# Stick_IMUinator_v2_1.net
KiCad netlist of a schematic drawn in EAGLE
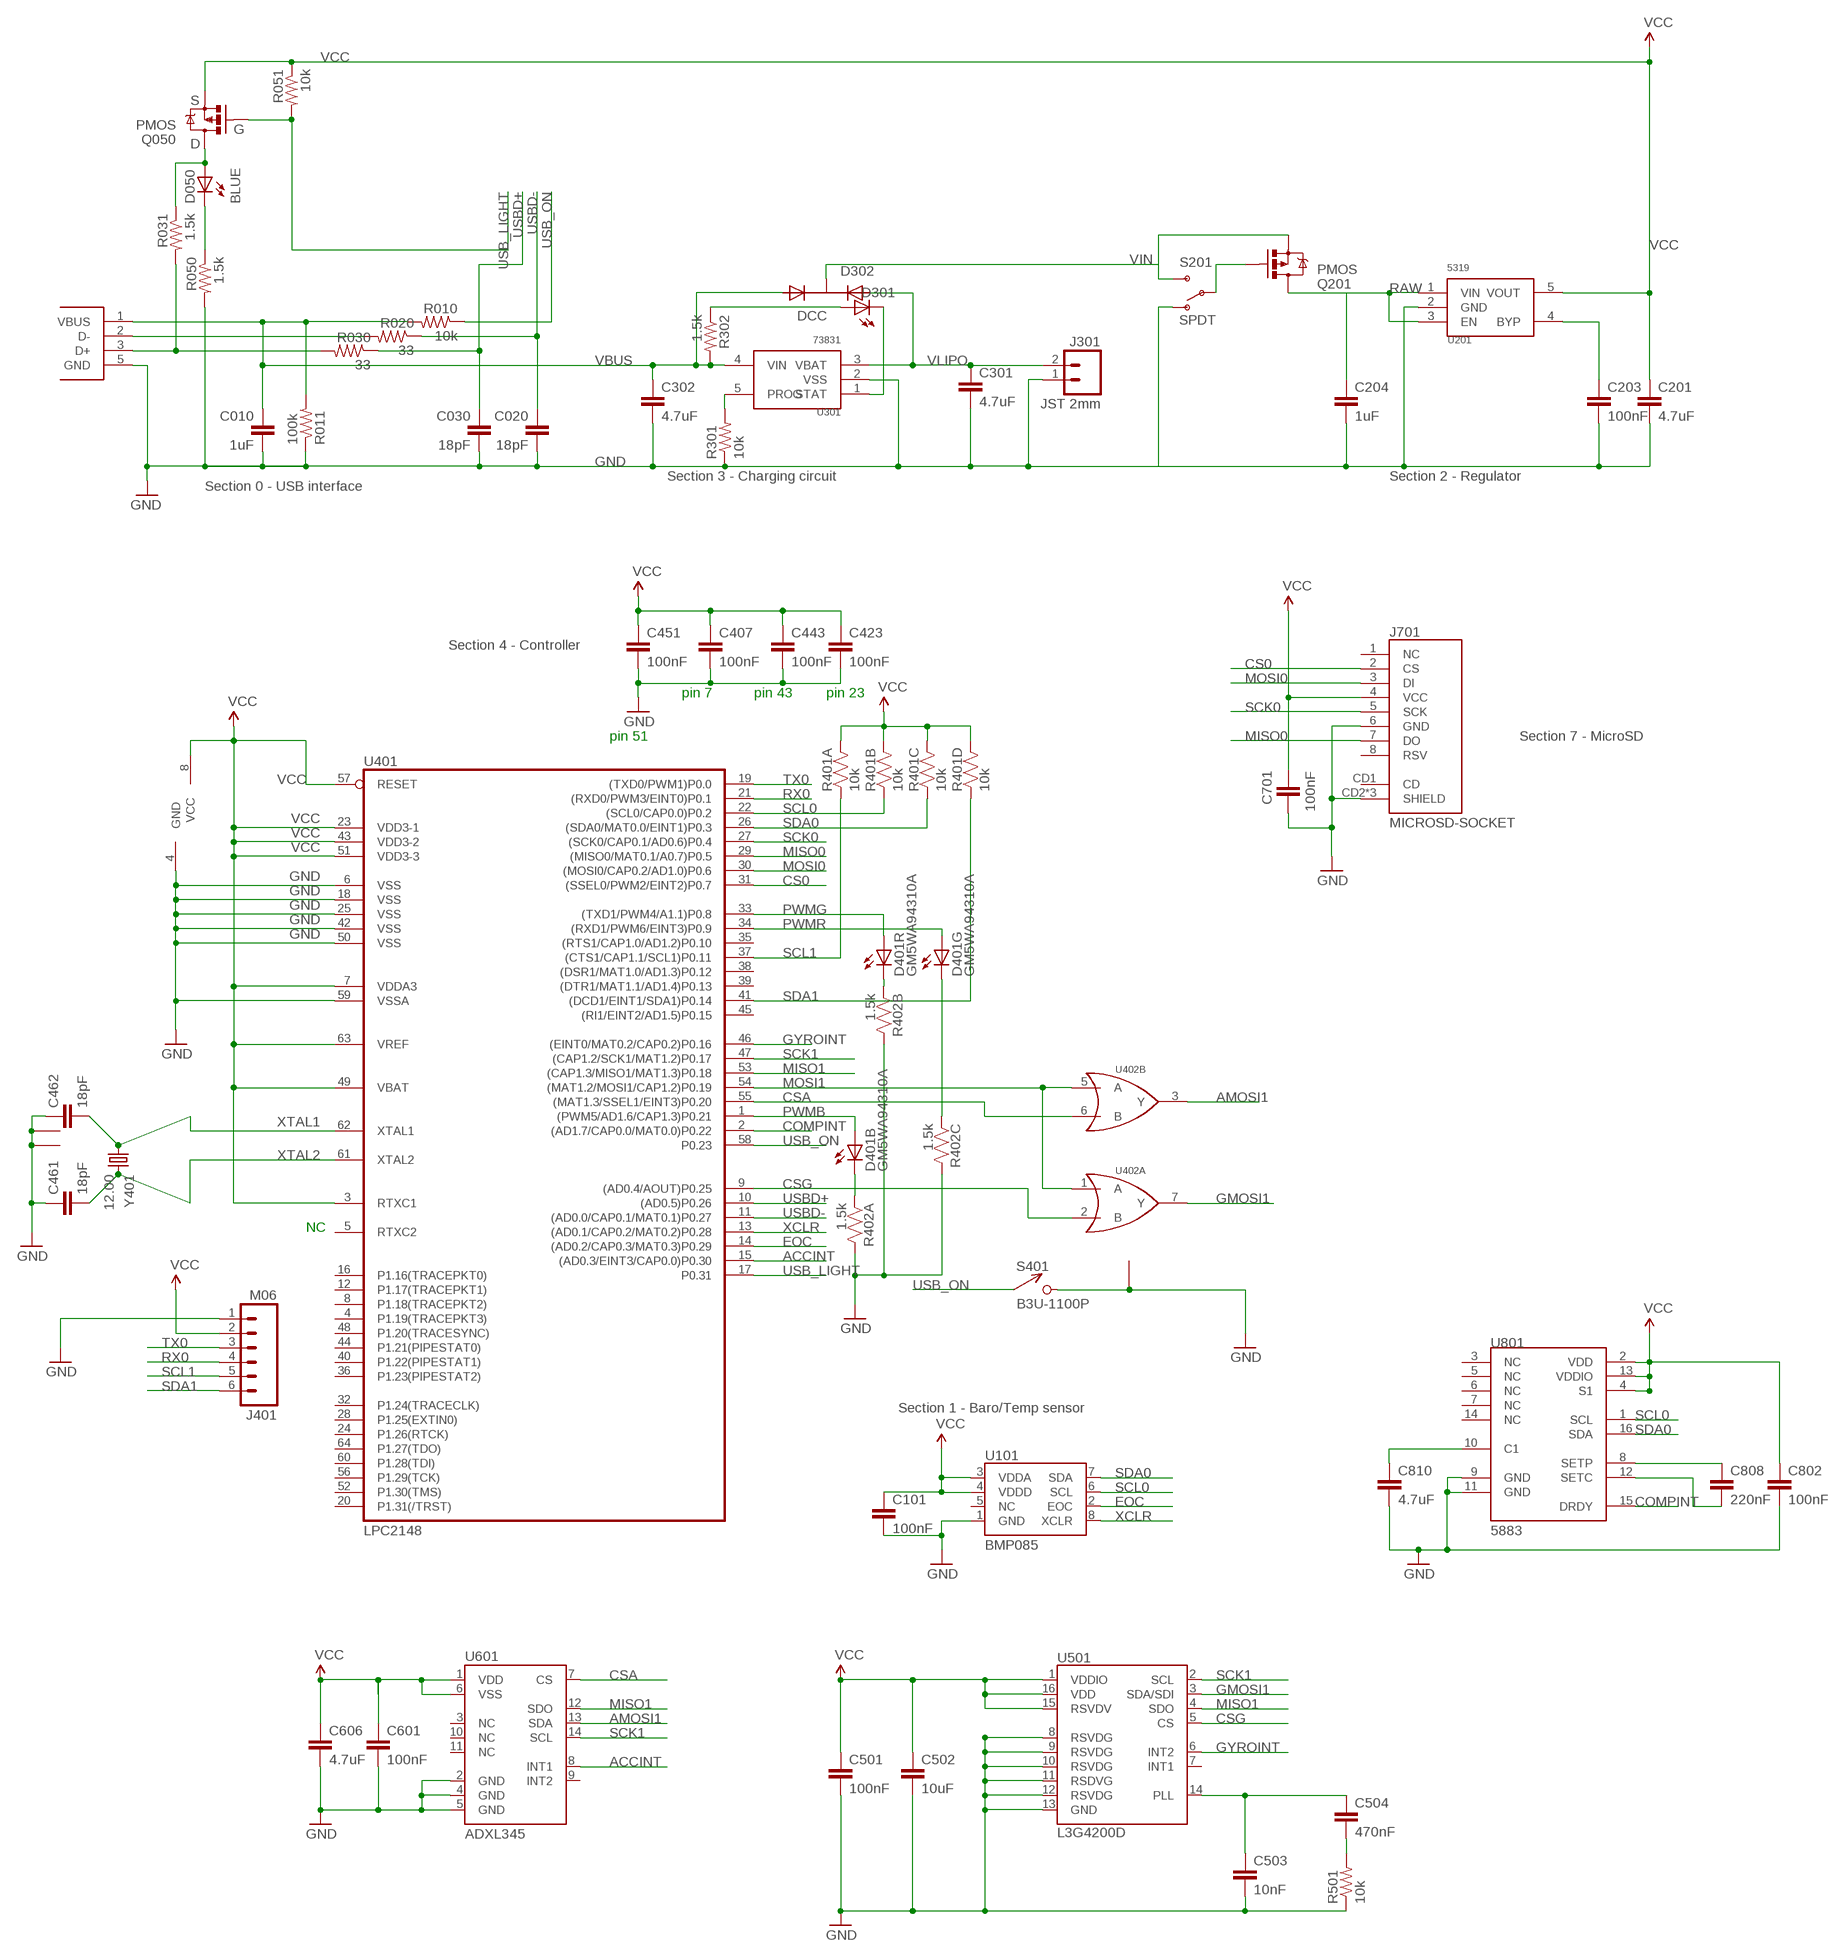
[diagram p0: schematic, sheet 1]

(export (version "E")
  (design (tool "Eeschema 10.0.6"))
  (components
    (comp (ref "C010")
      (value "1uF")
      (footprint "eagle-import:0402-CAP")
      (libsource (lib "eagle-import") (part "CAP0402-CAP"))
    )
    (comp (ref "C020")
      (value "18pF")
      (footprint "eagle-import:0402-CAP")
      (libsource (lib "eagle-import") (part "CAP0402-CAP"))
    )
    (comp (ref "C030")
      (value "18pF")
      (footprint "eagle-import:0402-CAP")
      (libsource (lib "eagle-import") (part "CAP0402-CAP"))
    )
    (comp (ref "C101")
      (value "100nF")
      (footprint "eagle-import:0402-CAP")
      (libsource (lib "eagle-import") (part "CAP0402-CAP"))
    )
    (comp (ref "C201")
      (value "4.7uF")
      (footprint "eagle-import:0402-CAP")
      (libsource (lib "eagle-import") (part "CAP0402-CAP"))
    )
    (comp (ref "C203")
      (value "100nF")
      (footprint "eagle-import:0402-CAP")
      (libsource (lib "eagle-import") (part "CAP0402-CAP"))
    )
    (comp (ref "C204")
      (value "1uF")
      (footprint "eagle-import:0402-CAP")
      (libsource (lib "eagle-import") (part "CAP0402-CAP"))
    )
    (comp (ref "C301")
      (value "4.7uF")
      (footprint "eagle-import:0402-CAP")
      (libsource (lib "eagle-import") (part "CAP0402-CAP"))
    )
    (comp (ref "C302")
      (value "4.7uF")
      (footprint "eagle-import:0402-CAP")
      (libsource (lib "eagle-import") (part "CAP0402-CAP"))
    )
    (comp (ref "C407")
      (value "100nF")
      (footprint "eagle-import:0402-CAP")
      (libsource (lib "eagle-import") (part "CAP0402-CAP"))
    )
    (comp (ref "C423")
      (value "100nF")
      (footprint "eagle-import:0402-CAP")
      (libsource (lib "eagle-import") (part "CAP0402-CAP"))
    )
    (comp (ref "C443")
      (value "100nF")
      (footprint "eagle-import:0402-CAP")
      (libsource (lib "eagle-import") (part "CAP0402-CAP"))
    )
    (comp (ref "C451")
      (value "100nF")
      (footprint "eagle-import:0402-CAP")
      (libsource (lib "eagle-import") (part "CAP0402-CAP"))
    )
    (comp (ref "C461")
      (value "18pF")
      (footprint "eagle-import:0402-CAP")
      (libsource (lib "eagle-import") (part "CAP0402-CAP"))
    )
    (comp (ref "C462")
      (value "18pF")
      (footprint "eagle-import:0402-CAP")
      (libsource (lib "eagle-import") (part "CAP0402-CAP"))
    )
    (comp (ref "C501")
      (value "100nF")
      (footprint "eagle-import:0402-CAP")
      (libsource (lib "eagle-import") (part "CAP0402-CAP"))
    )
    (comp (ref "C502")
      (value "10uF")
      (footprint "eagle-import:0603-CAP")
      (libsource (lib "eagle-import") (part "CAP0603-CAP"))
    )
    (comp (ref "C503")
      (value "10nF")
      (footprint "eagle-import:0402-CAP")
      (libsource (lib "eagle-import") (part "CAP0402-CAP"))
    )
    (comp (ref "C504")
      (value "470nF")
      (footprint "eagle-import:0402-CAP")
      (libsource (lib "eagle-import") (part "CAP0402-CAP"))
    )
    (comp (ref "C601")
      (value "100nF")
      (footprint "eagle-import:0402-CAP")
      (libsource (lib "eagle-import") (part "CAP0402-CAP"))
    )
    (comp (ref "C606")
      (value "4.7uF")
      (footprint "eagle-import:0402-CAP")
      (libsource (lib "eagle-import") (part "CAP0402-CAP"))
    )
    (comp (ref "C701")
      (value "100nF")
      (footprint "eagle-import:0402-CAP")
      (libsource (lib "eagle-import") (part "CAP0402-CAP"))
    )
    (comp (ref "C802")
      (value "100nF")
      (footprint "eagle-import:0402-CAP")
      (libsource (lib "eagle-import") (part "CAP0402-CAP"))
    )
    (comp (ref "C808")
      (value "220nF")
      (footprint "eagle-import:0402-CAP")
      (libsource (lib "eagle-import") (part "CAP0402-CAP"))
    )
    (comp (ref "C810")
      (value "4.7uF")
      (footprint "eagle-import:0402-CAP")
      (libsource (lib "eagle-import") (part "CAP0402-CAP"))
    )
    (comp (ref "D050")
      (value "BLUE")
      (footprint "eagle-import:LED-0603")
      (libsource (lib "eagle-import") (part "LED0603"))
    )
    (comp (ref "D301")
      (value "YELLOW")
      (footprint "eagle-import:LED-0603")
      (libsource (lib "eagle-import") (part "LED0603"))
    )
    (comp (ref "D302")
      (value "DCC")
      (footprint "eagle-import:SOT-23-3")
      (libsource (lib "eagle-import") (part "PMEG2005CT"))
    )
    (comp (ref "D401")
      (value "GM5WA94310A")
      (footprint "eagle-import:GM5WA94310A")
      (fields (field (name "DIGIKEY") "425-2728-1-ND"))
      (libsource (lib "eagle-import") (part "GM5WA94310A"))
    )
    (comp (ref "J001")
      (value "USB_MICROB_JST")
      (footprint "eagle-import:UB-MC5BR3-SD204-4S")
      (libsource (lib "eagle-import") (part "USB_MICROB_JST"))
    )
    (comp (ref "J301")
      (value "JST 2mm")
      (footprint "eagle-import:JST-2-SMD")
      (libsource (lib "eagle-import") (part "M02-JST-2MM-SMT"))
    )
    (comp (ref "J401")
      (value "M06")
      (footprint "eagle-import:1X06_LOCK")
      (libsource (lib "eagle-import") (part "M06LOCK"))
    )
    (comp (ref "J701")
      (value "MICROSD-SOCKET")
      (footprint "eagle-import:MICROSD-SOCKET-PP")
      (libsource (lib "eagle-import") (part "MICROSD-SOCKET"))
    )
    (comp (ref "Q050")
      (value "PMOS")
      (footprint "eagle-import:SOT23-3")
      (libsource (lib "eagle-import") (part "MOSFET-PCHANNELSMD"))
    )
    (comp (ref "Q201")
      (value "PMOS")
      (footprint "eagle-import:SOT23-3")
      (libsource (lib "eagle-import") (part "MOSFET-PCHANNELSMD"))
    )
    (comp (ref "R010")
      (value "10k")
      (footprint "eagle-import:0402-RES")
      (libsource (lib "eagle-import") (part "RESISTOR0402-RES"))
    )
    (comp (ref "R011")
      (value "100k")
      (footprint "eagle-import:0402-RES")
      (libsource (lib "eagle-import") (part "RESISTOR0402-RES"))
    )
    (comp (ref "R020")
      (value "33")
      (footprint "eagle-import:0402-RES")
      (libsource (lib "eagle-import") (part "RESISTOR0402-RES"))
    )
    (comp (ref "R030")
      (value "33")
      (footprint "eagle-import:0402-RES")
      (libsource (lib "eagle-import") (part "RESISTOR0402-RES"))
    )
    (comp (ref "R031")
      (value "1.5k")
      (footprint "eagle-import:0402-RES")
      (libsource (lib "eagle-import") (part "RESISTOR0402-RES"))
    )
    (comp (ref "R050")
      (value "1.5k")
      (footprint "eagle-import:0402-RES")
      (libsource (lib "eagle-import") (part "RESISTOR0402-RES"))
    )
    (comp (ref "R051")
      (value "10k")
      (footprint "eagle-import:0402-RES")
      (libsource (lib "eagle-import") (part "RESISTOR0402-RES"))
    )
    (comp (ref "R301")
      (value "10k")
      (footprint "eagle-import:0402-RES")
      (libsource (lib "eagle-import") (part "RESISTOR0402-RES"))
    )
    (comp (ref "R302")
      (value "1.5k")
      (footprint "eagle-import:0402-RES")
      (libsource (lib "eagle-import") (part "RESISTOR0402-RES"))
    )
    (comp (ref "R401")
      (value "10k")
      (footprint "eagle-import:CRA04")
      (fields (field (name "DIGIKEY") "CRA4S810KCT-ND"))
      (libsource (lib "eagle-import") (part "RP404"))
    )
    (comp (ref "R402")
      (value "1.5k")
      (footprint "eagle-import:CRA04")
      (fields (field (name "DIGIKEY") "CRA4S81.5KCT-ND"))
      (libsource (lib "eagle-import") (part "RP404"))
    )
    (comp (ref "R501")
      (value "10k")
      (footprint "eagle-import:0402-RES")
      (libsource (lib "eagle-import") (part "RESISTOR0402-RES"))
    )
    (comp (ref "S201")
      (value "SPDT")
      (footprint "eagle-import:AYZ0202")
      (libsource (lib "eagle-import") (part "SWITCH-SPSTSMD"))
    )
    (comp (ref "S401")
      (value "B3U-1100P")
      (footprint "eagle-import:B3U-1100P")
      (fields (field (name "DIGIKEY") "SW1021CT-ND"))
      (libsource (lib "eagle-import") (part "B3U-1100P"))
    )
    (comp (ref "U101")
      (value "BMP085")
      (footprint "eagle-import:BMP085")
      (libsource (lib "eagle-import") (part "BMP085"))
    )
    (comp (ref "U201")
      (value "5319")
      (footprint "eagle-import:SOT-23-5")
      (libsource (lib "eagle-import") (part "MIC5319D5"))
    )
    (comp (ref "U301")
      (value "73831")
      (footprint "eagle-import:SOT-23-5")
      (libsource (lib "eagle-import") (part "MCP73831"))
    )
    (comp (ref "U401")
      (value "LPC2148")
      (footprint "eagle-import:SQFP-S-10X10-64")
      (libsource (lib "eagle-import") (part "LPC213X"))
    )
    (comp (ref "U402")
      (value "7432")
      (footprint "eagle-import:DCU_8")
      (fields (field (name "DIGIKEY") "296-13268-1-ND"))
      (libsource (lib "eagle-import") (part "SN74LVC2G32"))
    )
    (comp (ref "U501")
      (value "L3G4200D")
      (footprint "eagle-import:LGA16-4X4")
      (libsource (lib "eagle-import") (part "L3G4200D"))
    )
    (comp (ref "U601")
      (value "ADXL345")
      (footprint "eagle-import:LGA14")
      (libsource (lib "eagle-import") (part "ADXL345"))
    )
    (comp (ref "U801")
      (value "5883")
      (footprint "eagle-import:16LPCC")
      (libsource (lib "eagle-import") (part "HMC5883LSMD"))
    )
    (comp (ref "Y401")
      (value "12.00")
      (footprint "eagle-import:CRYSTAL_SMD")
      (fields (field (name "DIGIKEY") "887-1316-1-ND"))
      (libsource (lib "eagle-import") (part "TSX-3225"))
    )
  )
  (nets
    (net (code "1") (name "/ACCINT") (class "Default")
      (node (ref "U401") (pin "15") (pinfunction "(AD0.3/EINT3/CAP0.0)P0.30_15") (pintype "bidirectional"))
      (node (ref "U601") (pin "8") (pinfunction "INT1_8") (pintype "bidirectional"))
    )
    (net (code "2") (name "/AMOSI1") (class "Default")
      (node (ref "U402") (pin "3") (pinfunction "Y_3") (pintype "bidirectional"))
      (node (ref "U601") (pin "13") (pinfunction "SDA_13") (pintype "bidirectional"))
    )
    (net (code "3") (name "/COMPINT") (class "Default")
      (node (ref "U401") (pin "2") (pinfunction "(AD1.7/CAP0.0/MAT0.0)P0.22_2") (pintype "bidirectional"))
      (node (ref "U801") (pin "15") (pinfunction "DRDY_15") (pintype "bidirectional"))
    )
    (net (code "4") (name "/CS0") (class "Default")
      (node (ref "J701") (pin "2") (pinfunction "CS_2") (pintype "bidirectional"))
      (node (ref "U401") (pin "31") (pinfunction "(SSEL0/PWM2/EINT2)P0.7_31") (pintype "bidirectional"))
    )
    (net (code "5") (name "/CSA") (class "Default")
      (node (ref "U401") (pin "55") (pinfunction "(MAT1.3/SSEL1/EINT3)P0.20_55") (pintype "bidirectional"))
      (node (ref "U402") (pin "6") (pinfunction "B_6") (pintype "bidirectional"))
      (node (ref "U601") (pin "7") (pinfunction "CS_7") (pintype "bidirectional"))
    )
    (net (code "6") (name "/CSG") (class "Default")
      (node (ref "U401") (pin "9") (pinfunction "(AD0.4/AOUT)P0.25_9") (pintype "bidirectional"))
      (node (ref "U402") (pin "2") (pinfunction "B_2") (pintype "bidirectional"))
      (node (ref "U501") (pin "5") (pinfunction "CS_5") (pintype "bidirectional"))
    )
    (net (code "7") (name "/EOC") (class "Default")
      (node (ref "U101") (pin "2") (pinfunction "EOC_2") (pintype "output"))
      (node (ref "U401") (pin "14") (pinfunction "(AD0.2/CAP0.3/MAT0.3)P0.29_14") (pintype "bidirectional"))
    )
    (net (code "8") (name "/GMOSI1") (class "Default")
      (node (ref "U402") (pin "7") (pinfunction "Y_7") (pintype "bidirectional"))
      (node (ref "U501") (pin "3") (pinfunction "SDA/SDI_3") (pintype "bidirectional"))
    )
    (net (code "9") (name "/GYROINT") (class "Default")
      (node (ref "U401") (pin "46") (pinfunction "(EINT0/MAT0.2/CAP0.2)P0.16_46") (pintype "bidirectional"))
      (node (ref "U501") (pin "6") (pinfunction "INT2_6") (pintype "bidirectional"))
    )
    (net (code "10") (name "/MISO0") (class "Default")
      (node (ref "J701") (pin "7") (pinfunction "DO_7") (pintype "bidirectional"))
      (node (ref "U401") (pin "29") (pinfunction "(MISO0/MAT0.1/A0.7)P0.5_29") (pintype "bidirectional"))
    )
    (net (code "11") (name "/MISO1") (class "Default")
      (node (ref "U401") (pin "53") (pinfunction "(CAP1.3/MISO1/MAT1.3)P0.18_53") (pintype "bidirectional"))
      (node (ref "U501") (pin "4") (pinfunction "SDO_4") (pintype "bidirectional"))
      (node (ref "U601") (pin "12") (pinfunction "SDO_12") (pintype "bidirectional"))
    )
    (net (code "12") (name "/MOSI0") (class "Default")
      (node (ref "J701") (pin "3") (pinfunction "DI_3") (pintype "bidirectional"))
      (node (ref "U401") (pin "30") (pinfunction "(MOSI0/CAP0.2/AD1.0)P0.6_30") (pintype "bidirectional"))
    )
    (net (code "13") (name "/MOSI1") (class "Default")
      (node (ref "U401") (pin "54") (pinfunction "(MAT1.2/MOSI1/CAP1.2)P0.19_54") (pintype "bidirectional"))
      (node (ref "U402") (pin "1") (pinfunction "A_1") (pintype "bidirectional"))
      (node (ref "U402") (pin "5") (pinfunction "A_5") (pintype "bidirectional"))
    )
    (net (code "14") (name "/PWMB") (class "Default")
      (node (ref "D401") (pin "1") (pinfunction "A_1") (pintype "passive"))
      (node (ref "U401") (pin "1") (pinfunction "(PWM5/AD1.6/CAP1.3)P0.21_1") (pintype "bidirectional"))
    )
    (net (code "15") (name "/PWMG") (class "Default")
      (node (ref "D401") (pin "3") (pinfunction "A_3") (pintype "passive"))
      (node (ref "U401") (pin "34") (pinfunction "(RXD1/PWM6/EINT3)P0.9_34") (pintype "bidirectional"))
    )
    (net (code "16") (name "/PWMR") (class "Default")
      (node (ref "D401") (pin "2") (pinfunction "A_2") (pintype "passive"))
      (node (ref "U401") (pin "33") (pinfunction "(TXD1/PWM4/A1.1)P0.8_33") (pintype "bidirectional"))
    )
    (net (code "17") (name "/RAW") (class "Default")
      (node (ref "C204") (pin "1") (pinfunction "1_1") (pintype "passive"))
      (node (ref "Q201") (pin "3") (pinfunction "D_3") (pintype "passive"))
      (node (ref "U201") (pin "1") (pinfunction "VIN_1") (pintype "bidirectional"))
      (node (ref "U201") (pin "3") (pinfunction "EN_3") (pintype "bidirectional"))
    )
    (net (code "18") (name "/RX0") (class "Default")
      (node (ref "J401") (pin "4") (pinfunction "4_4") (pintype "passive"))
      (node (ref "U401") (pin "21") (pinfunction "(RXD0/PWM3/EINT0)P0.1_21") (pintype "bidirectional"))
    )
    (net (code "19") (name "/SCK0") (class "Default")
      (node (ref "J701") (pin "5") (pinfunction "SCK_5") (pintype "bidirectional"))
      (node (ref "U401") (pin "27") (pinfunction "(SCK0/CAP0.1/AD0.6)P0.4_27") (pintype "bidirectional"))
    )
    (net (code "20") (name "/SCK1") (class "Default")
      (node (ref "U401") (pin "47") (pinfunction "(CAP1.2/SCK1/MAT1.2)P0.17_47") (pintype "bidirectional"))
      (node (ref "U501") (pin "2") (pinfunction "SCL_2") (pintype "bidirectional"))
      (node (ref "U601") (pin "14") (pinfunction "SCL_14") (pintype "bidirectional"))
    )
    (net (code "21") (name "/SCL0") (class "Default")
      (node (ref "R401") (pin "2") (pinfunction "1_2") (pintype "passive"))
      (node (ref "U101") (pin "6") (pinfunction "SCL_6") (pintype "input"))
      (node (ref "U401") (pin "22") (pinfunction "(SCL0/CAP0.0)P0.2_22") (pintype "bidirectional"))
      (node (ref "U801") (pin "1") (pinfunction "SCL_1") (pintype "bidirectional"))
    )
    (net (code "22") (name "/SCL1") (class "Default")
      (node (ref "J401") (pin "5") (pinfunction "5_5") (pintype "passive"))
      (node (ref "R401") (pin "1") (pinfunction "1_1") (pintype "passive"))
      (node (ref "U401") (pin "37") (pinfunction "(CTS1/CAP1.1/SCL1)P0.11_37") (pintype "bidirectional"))
    )
    (net (code "23") (name "/SDA0") (class "Default")
      (node (ref "R401") (pin "3") (pinfunction "1_3") (pintype "passive"))
      (node (ref "U101") (pin "7") (pinfunction "SDA_7") (pintype "bidirectional"))
      (node (ref "U401") (pin "26") (pinfunction "(SDA0/MAT0.0/EINT1)P0.3_26") (pintype "bidirectional"))
      (node (ref "U801") (pin "16") (pinfunction "SDA_16") (pintype "bidirectional"))
    )
    (net (code "24") (name "/SDA1") (class "Default")
      (node (ref "J401") (pin "6") (pinfunction "6_6") (pintype "passive"))
      (node (ref "R401") (pin "4") (pinfunction "1_4") (pintype "passive"))
      (node (ref "U401") (pin "41") (pinfunction "(DCD1/EINT1/SDA1)P0.14_41") (pintype "bidirectional"))
    )
    (net (code "25") (name "/TX0") (class "Default")
      (node (ref "J401") (pin "3") (pinfunction "3_3") (pintype "passive"))
      (node (ref "U401") (pin "19") (pinfunction "(TXD0/PWM1)P0.0_19") (pintype "bidirectional"))
    )
    (net (code "26") (name "/USBD+") (class "Default")
      (node (ref "C030") (pin "1") (pinfunction "1_1") (pintype "passive"))
      (node (ref "R030") (pin "1") (pinfunction "1_1") (pintype "passive"))
      (node (ref "U401") (pin "10") (pinfunction "(AD0.5)P0.26_10") (pintype "bidirectional"))
    )
    (net (code "27") (name "/USBD-") (class "Default")
      (node (ref "C020") (pin "1") (pinfunction "1_1") (pintype "passive"))
      (node (ref "R020") (pin "1") (pinfunction "1_1") (pintype "passive"))
      (node (ref "U401") (pin "11") (pinfunction "(AD0.0/CAP0.1/MAT0.1)P0.27_11") (pintype "bidirectional"))
    )
    (net (code "28") (name "/USB_LIGHT") (class "Default")
      (node (ref "Q050") (pin "1") (pinfunction "G_1") (pintype "passive"))
      (node (ref "R051") (pin "2") (pinfunction "2_2") (pintype "passive"))
      (node (ref "U401") (pin "17") (pinfunction "P0.31_17") (pintype "output"))
    )
    (net (code "29") (name "/USB_ON") (class "Default")
      (node (ref "R010") (pin "1") (pinfunction "1_1") (pintype "passive"))
      (node (ref "S401") (pin "P$1") (pinfunction "1_P$1") (pintype "bidirectional"))
      (node (ref "U401") (pin "58") (pinfunction "P0.23_58") (pintype "bidirectional"))
    )
    (net (code "30") (name "/VBUS") (class "Default")
      (node (ref "C010") (pin "1") (pinfunction "1_1") (pintype "passive"))
      (node (ref "C302") (pin "1") (pinfunction "1_1") (pintype "passive"))
      (node (ref "D302") (pin "1") (pinfunction "A1_1") (pintype "passive"))
      (node (ref "J001") (pin "1") (pinfunction "VBUS_1") (pintype "bidirectional"))
      (node (ref "R010") (pin "2") (pinfunction "2_2") (pintype "passive"))
      (node (ref "R011") (pin "2") (pinfunction "2_2") (pintype "passive"))
      (node (ref "R302") (pin "2") (pinfunction "2_2") (pintype "passive"))
      (node (ref "U301") (pin "4") (pinfunction "VIN_4") (pintype "bidirectional"))
    )
    (net (code "31") (name "/VIN") (class "Default")
      (node (ref "D302") (pin "3") (pinfunction "K_3") (pintype "passive"))
      (node (ref "Q201") (pin "2") (pinfunction "S_2") (pintype "passive"))
      (node (ref "S201") (pin "3") (pinfunction "S_3") (pintype "passive"))
    )
    (net (code "32") (name "/VLIPO") (class "Default")
      (node (ref "C301") (pin "1") (pinfunction "1_1") (pintype "passive"))
      (node (ref "D302") (pin "2") (pinfunction "A2_2") (pintype "passive"))
      (node (ref "J301") (pin "2") (pinfunction "2_2") (pintype "passive"))
      (node (ref "U301") (pin "3") (pinfunction "VBAT_3") (pintype "bidirectional"))
    )
    (net (code "33") (name "/XCLR") (class "Default")
      (node (ref "U101") (pin "8") (pinfunction "XCLR_8") (pintype "input"))
      (node (ref "U401") (pin "13") (pinfunction "(AD0.1/CAP0.2/MAT0.2)P0.28_13") (pintype "bidirectional"))
    )
    (net (code "34") (name "/XTAL1") (class "Default")
      (node (ref "C462") (pin "2") (pinfunction "2_2") (pintype "passive"))
      (node (ref "U401") (pin "62") (pinfunction "XTAL1_62") (pintype "input"))
      (node (ref "Y401") (pin "1") (pinfunction "1_1") (pintype "passive"))
    )
    (net (code "35") (name "/XTAL2") (class "Default")
      (node (ref "C461") (pin "2") (pinfunction "2_2") (pintype "passive"))
      (node (ref "U401") (pin "61") (pinfunction "XTAL2_61") (pintype "output"))
      (node (ref "Y401") (pin "3") (pinfunction "2_3") (pintype "passive"))
    )
    (net (code "36") (name "GND") (class "Default")
      (node (ref "C010") (pin "2") (pinfunction "2_2") (pintype "passive"))
      (node (ref "C020") (pin "2") (pinfunction "2_2") (pintype "passive"))
      (node (ref "C030") (pin "2") (pinfunction "2_2") (pintype "passive"))
      (node (ref "C101") (pin "2") (pinfunction "2_2") (pintype "passive"))
      (node (ref "C201") (pin "2") (pinfunction "2_2") (pintype "passive"))
      (node (ref "C203") (pin "2") (pinfunction "2_2") (pintype "passive"))
      (node (ref "C204") (pin "2") (pinfunction "2_2") (pintype "passive"))
      (node (ref "C301") (pin "2") (pinfunction "2_2") (pintype "passive"))
      (node (ref "C302") (pin "2") (pinfunction "2_2") (pintype "passive"))
      (node (ref "C407") (pin "2") (pinfunction "2_2") (pintype "passive"))
      (node (ref "C423") (pin "2") (pinfunction "2_2") (pintype "passive"))
      (node (ref "C443") (pin "2") (pinfunction "2_2") (pintype "passive"))
      (node (ref "C451") (pin "2") (pinfunction "2_2") (pintype "passive"))
      (node (ref "C461") (pin "1") (pinfunction "1_1") (pintype "passive"))
      (node (ref "C462") (pin "1") (pinfunction "1_1") (pintype "passive"))
      (node (ref "C501") (pin "2") (pinfunction "2_2") (pintype "passive"))
      (node (ref "C502") (pin "2") (pinfunction "2_2") (pintype "passive"))
      (node (ref "C503") (pin "2") (pinfunction "2_2") (pintype "passive"))
      (node (ref "C601") (pin "2") (pinfunction "2_2") (pintype "passive"))
      (node (ref "C606") (pin "2") (pinfunction "2_2") (pintype "passive"))
      (node (ref "C701") (pin "2") (pinfunction "2_2") (pintype "passive"))
      (node (ref "C802") (pin "2") (pinfunction "2_2") (pintype "passive"))
      (node (ref "C810") (pin "2") (pinfunction "2_2") (pintype "passive"))
      (node (ref "J001") (pin "5") (pinfunction "GND_5") (pintype "bidirectional"))
      (node (ref "J301") (pin "1") (pinfunction "1_1") (pintype "passive"))
      (node (ref "J401") (pin "1") (pinfunction "1_1") (pintype "passive"))
      (node (ref "J701") (pin "6") (pinfunction "GND_6") (pintype "bidirectional"))
      (node (ref "J701") (pin "CD2") (pinfunction "SHIELD_CD2") (pintype "bidirectional"))
      (node (ref "J701") (pin "GND1") (pinfunction "SHIELD_GND1") (pintype "bidirectional"))
      (node (ref "J701") (pin "GND3") (pinfunction "SHIELD_GND3") (pintype "bidirectional"))
      (node (ref "R011") (pin "1") (pinfunction "1_1") (pintype "passive"))
      (node (ref "R050") (pin "2") (pinfunction "2_2") (pintype "passive"))
      (node (ref "R301") (pin "1") (pinfunction "1_1") (pintype "passive"))
      (node (ref "R402") (pin "6") (pinfunction "2_6") (pintype "passive"))
      (node (ref "R402") (pin "7") (pinfunction "2_7") (pintype "passive"))
      (node (ref "R402") (pin "8") (pinfunction "2_8") (pintype "passive"))
      (node (ref "R501") (pin "1") (pinfunction "1_1") (pintype "passive"))
      (node (ref "S201") (pin "1") (pinfunction "O_1") (pintype "passive"))
      (node (ref "S401") (pin "P$2") (pinfunction "2_P$2") (pintype "bidirectional"))
      (node (ref "S401") (pin "P$3") (pinfunction "1_P$3") (pintype "bidirectional"))
      (node (ref "U101") (pin "1") (pinfunction "GND_1") (pintype "power_in"))
      (node (ref "U201") (pin "2") (pinfunction "GND_2") (pintype "bidirectional"))
      (node (ref "U301") (pin "2") (pinfunction "VSS_2") (pintype "bidirectional"))
      (node (ref "U401") (pin "18") (pinfunction "VSS_18") (pintype "power_in"))
      (node (ref "U401") (pin "25") (pinfunction "VSS_25") (pintype "power_in"))
      (node (ref "U401") (pin "42") (pinfunction "VSS_42") (pintype "power_in"))
      (node (ref "U401") (pin "50") (pinfunction "VSS_50") (pintype "power_in"))
      (node (ref "U401") (pin "59") (pinfunction "VSSA_59") (pintype "power_in"))
      (node (ref "U401") (pin "6") (pinfunction "VSS_6") (pintype "power_in"))
      (node (ref "U402") (pin "4") (pinfunction "GND_4") (pintype "bidirectional"))
      (node (ref "U501") (pin "10") (pinfunction "RSVDG_10") (pintype "bidirectional"))
      (node (ref "U501") (pin "11") (pinfunction "RSDVG_11") (pintype "bidirectional"))
      (node (ref "U501") (pin "12") (pinfunction "RSVDG_12") (pintype "bidirectional"))
      (node (ref "U501") (pin "13") (pinfunction "GND_13") (pintype "bidirectional"))
      (node (ref "U501") (pin "8") (pinfunction "RSVDG_8") (pintype "bidirectional"))
      (node (ref "U501") (pin "9") (pinfunction "RSVDG_9") (pintype "bidirectional"))
      (node (ref "U601") (pin "2") (pinfunction "GND_2") (pintype "bidirectional"))
      (node (ref "U601") (pin "4") (pinfunction "GND_4") (pintype "bidirectional"))
      (node (ref "U601") (pin "5") (pinfunction "GND_5") (pintype "bidirectional"))
      (node (ref "U801") (pin "11") (pinfunction "GND_11") (pintype "bidirectional"))
      (node (ref "U801") (pin "9") (pinfunction "GND_9") (pintype "bidirectional"))
      (node (ref "Y401") (pin "2") (pinfunction "1_2") (pintype "bidirectional"))
      (node (ref "Y401") (pin "4") (pinfunction "1_4") (pintype "bidirectional"))
    )
    (net (code "37") (name "Net-(C504-Pad2)") (class "Default")
      (node (ref "C504") (pin "2") (pinfunction "2_2") (pintype "passive"))
      (node (ref "R501") (pin "2") (pinfunction "2_2") (pintype "passive"))
    )
    (net (code "38") (name "Net-(D050-PadC)") (class "Default")
      (node (ref "D050") (pin "C") (pinfunction "C_C") (pintype "passive"))
      (node (ref "R050") (pin "1") (pinfunction "1_1") (pintype "passive"))
    )
    (net (code "39") (name "Net-(D301-PadA)") (class "Default")
      (node (ref "D301") (pin "A") (pinfunction "A_A") (pintype "passive"))
      (node (ref "R302") (pin "1") (pinfunction "1_1") (pintype "passive"))
    )
    (net (code "40") (name "Net-(D401A-C)") (class "Default")
      (node (ref "D401") (pin "6") (pinfunction "C_6") (pintype "passive"))
      (node (ref "R402") (pin "1") (pinfunction "1_1") (pintype "passive"))
    )
    (net (code "41") (name "Net-(D401B-C)") (class "Default")
      (node (ref "D401") (pin "4") (pinfunction "C_4") (pintype "passive"))
      (node (ref "R402") (pin "3") (pinfunction "1_3") (pintype "passive"))
    )
    (net (code "42") (name "Net-(D401C-C)") (class "Default")
      (node (ref "D401") (pin "5") (pinfunction "C_5") (pintype "passive"))
      (node (ref "R402") (pin "2") (pinfunction "1_2") (pintype "passive"))
    )
    (net (code "43") (name "Net-(J001-D+)") (class "Default")
      (node (ref "J001") (pin "3") (pinfunction "D+_3") (pintype "bidirectional"))
      (node (ref "R030") (pin "2") (pinfunction "2_2") (pintype "passive"))
      (node (ref "R031") (pin "2") (pinfunction "2_2") (pintype "passive"))
    )
    (net (code "44") (name "Net-(J001-D-)") (class "Default")
      (node (ref "J001") (pin "2") (pinfunction "D-_2") (pintype "bidirectional"))
      (node (ref "R020") (pin "2") (pinfunction "2_2") (pintype "passive"))
    )
    (net (code "45") (name "Net-(Q050-D)") (class "Default")
      (node (ref "D050") (pin "A") (pinfunction "A_A") (pintype "passive"))
      (node (ref "Q050") (pin "3") (pinfunction "D_3") (pintype "passive"))
      (node (ref "R031") (pin "1") (pinfunction "1_1") (pintype "passive"))
    )
    (net (code "46") (name "Net-(Q201-G)") (class "Default")
      (node (ref "Q201") (pin "1") (pinfunction "G_1") (pintype "passive"))
      (node (ref "S201") (pin "2") (pinfunction "P_2") (pintype "passive"))
    )
    (net (code "47") (name "Net-(U201-BYP)") (class "Default")
      (node (ref "C203") (pin "1") (pinfunction "1_1") (pintype "passive"))
      (node (ref "U201") (pin "4") (pinfunction "BYP_4") (pintype "bidirectional"))
    )
    (net (code "48") (name "Net-(U301-PROG)") (class "Default")
      (node (ref "R301") (pin "2") (pinfunction "2_2") (pintype "passive"))
      (node (ref "U301") (pin "5") (pinfunction "PROG_5") (pintype "bidirectional"))
    )
    (net (code "49") (name "Net-(U301-STAT)") (class "Default")
      (node (ref "D301") (pin "C") (pinfunction "C_C") (pintype "passive"))
      (node (ref "U301") (pin "1") (pinfunction "STAT_1") (pintype "bidirectional"))
    )
    (net (code "50") (name "Net-(U501-PLL)") (class "Default")
      (node (ref "C503") (pin "1") (pinfunction "1_1") (pintype "passive"))
      (node (ref "C504") (pin "1") (pinfunction "1_1") (pintype "passive"))
      (node (ref "U501") (pin "14") (pinfunction "PLL_14") (pintype "bidirectional"))
    )
    (net (code "51") (name "Net-(U801-C1)") (class "Default")
      (node (ref "C810") (pin "1") (pinfunction "1_1") (pintype "passive"))
      (node (ref "U801") (pin "10") (pinfunction "C1_10") (pintype "bidirectional"))
    )
    (net (code "52") (name "Net-(U801-SETC)") (class "Default")
      (node (ref "C808") (pin "2") (pinfunction "2_2") (pintype "passive"))
      (node (ref "U801") (pin "12") (pinfunction "SETC_12") (pintype "bidirectional"))
    )
    (net (code "53") (name "Net-(U801-SETP)") (class "Default")
      (node (ref "C808") (pin "1") (pinfunction "1_1") (pintype "passive"))
      (node (ref "U801") (pin "8") (pinfunction "SETP_8") (pintype "bidirectional"))
    )
    (net (code "54") (name "VCC") (class "Default")
      (node (ref "C101") (pin "1") (pinfunction "1_1") (pintype "passive"))
      (node (ref "C201") (pin "1") (pinfunction "1_1") (pintype "passive"))
      (node (ref "C407") (pin "1") (pinfunction "1_1") (pintype "passive"))
      (node (ref "C423") (pin "1") (pinfunction "1_1") (pintype "passive"))
      (node (ref "C443") (pin "1") (pinfunction "1_1") (pintype "passive"))
      (node (ref "C451") (pin "1") (pinfunction "1_1") (pintype "passive"))
      (node (ref "C501") (pin "1") (pinfunction "1_1") (pintype "passive"))
      (node (ref "C502") (pin "1") (pinfunction "1_1") (pintype "passive"))
      (node (ref "C601") (pin "1") (pinfunction "1_1") (pintype "passive"))
      (node (ref "C606") (pin "1") (pinfunction "1_1") (pintype "passive"))
      (node (ref "C701") (pin "1") (pinfunction "1_1") (pintype "passive"))
      (node (ref "C802") (pin "1") (pinfunction "1_1") (pintype "passive"))
      (node (ref "J401") (pin "2") (pinfunction "2_2") (pintype "passive"))
      (node (ref "J701") (pin "4") (pinfunction "VCC_4") (pintype "bidirectional"))
      (node (ref "Q050") (pin "2") (pinfunction "S_2") (pintype "passive"))
      (node (ref "R051") (pin "1") (pinfunction "1_1") (pintype "passive"))
      (node (ref "R401") (pin "5") (pinfunction "2_5") (pintype "passive"))
      (node (ref "R401") (pin "6") (pinfunction "2_6") (pintype "passive"))
      (node (ref "R401") (pin "7") (pinfunction "2_7") (pintype "passive"))
      (node (ref "R401") (pin "8") (pinfunction "2_8") (pintype "passive"))
      (node (ref "U101") (pin "3") (pinfunction "VDDA_3") (pintype "power_in"))
      (node (ref "U101") (pin "4") (pinfunction "VDDD_4") (pintype "power_in"))
      (node (ref "U201") (pin "5") (pinfunction "VOUT_5") (pintype "bidirectional"))
      (node (ref "U401") (pin "23") (pinfunction "VDD3-1_23") (pintype "power_in"))
      (node (ref "U401") (pin "3") (pinfunction "RTXC1_3") (pintype "input"))
      (node (ref "U401") (pin "43") (pinfunction "VDD3-2_43") (pintype "power_in"))
      (node (ref "U401") (pin "49") (pinfunction "VBAT_49") (pintype "power_in"))
      (node (ref "U401") (pin "51") (pinfunction "VDD3-3_51") (pintype "power_in"))
      (node (ref "U401") (pin "57") (pinfunction "RESET_57") (pintype "input"))
      (node (ref "U401") (pin "63") (pinfunction "VREF_63") (pintype "input"))
      (node (ref "U401") (pin "7") (pinfunction "VDDA3_7") (pintype "power_in"))
      (node (ref "U402") (pin "8") (pinfunction "VCC_8") (pintype "bidirectional"))
      (node (ref "U501") (pin "1") (pinfunction "VDDIO_1") (pintype "bidirectional"))
      (node (ref "U501") (pin "15") (pinfunction "RSVDV_15") (pintype "bidirectional"))
      (node (ref "U501") (pin "16") (pinfunction "VDD_16") (pintype "bidirectional"))
      (node (ref "U601") (pin "1") (pinfunction "VDD_1") (pintype "bidirectional"))
      (node (ref "U601") (pin "6") (pinfunction "VSS_6") (pintype "bidirectional"))
      (node (ref "U801") (pin "13") (pinfunction "VDDIO_13") (pintype "bidirectional"))
      (node (ref "U801") (pin "2") (pinfunction "VDD_2") (pintype "bidirectional"))
      (node (ref "U801") (pin "4") (pinfunction "S1_4") (pintype "bidirectional"))
    )
    (net (code "55") (name "unconnected-(J701-CD-PadCD1)") (class "Default")
      (node (ref "J701") (pin "CD1") (pinfunction "CD_CD1") (pintype "bidirectional"))
    )
    (net (code "56") (name "unconnected-(J701-NC-Pad1)") (class "Default")
      (node (ref "J701") (pin "1") (pinfunction "NC_1") (pintype "bidirectional"))
    )
    (net (code "57") (name "unconnected-(J701-RSV-Pad8)") (class "Default")
      (node (ref "J701") (pin "8") (pinfunction "RSV_8") (pintype "bidirectional"))
    )
    (net (code "58") (name "unconnected-(U101-NC-Pad5)") (class "Default")
      (node (ref "U101") (pin "5") (pinfunction "NC_5") (pintype "bidirectional"))
    )
    (net (code "59") (name "unconnected-(U401-(DSR1{slash}MAT1.0{slash}AD1.3)P0.12-Pad38)") (class "Default")
      (node (ref "U401") (pin "38") (pinfunction "(DSR1/MAT1.0/AD1.3)P0.12_38") (pintype "bidirectional"))
    )
    (net (code "60") (name "unconnected-(U401-(DTR1{slash}MAT1.1{slash}AD1.4)P0.13-Pad39)") (class "Default")
      (node (ref "U401") (pin "39") (pinfunction "(DTR1/MAT1.1/AD1.4)P0.13_39") (pintype "bidirectional"))
    )
    (net (code "61") (name "unconnected-(U401-(RI1{slash}EINT2{slash}AD1.5)P0.15-Pad45)") (class "Default")
      (node (ref "U401") (pin "45") (pinfunction "(RI1/EINT2/AD1.5)P0.15_45") (pintype "bidirectional"))
    )
    (net (code "62") (name "unconnected-(U401-(RTS1{slash}CAP1.0{slash}AD1.2)P0.10-Pad35)") (class "Default")
      (node (ref "U401") (pin "35") (pinfunction "(RTS1/CAP1.0/AD1.2)P0.10_35") (pintype "bidirectional"))
    )
    (net (code "63") (name "unconnected-(U401-P1.16(TRACEPKT0)-Pad16)") (class "Default")
      (node (ref "U401") (pin "16") (pinfunction "P1.16(TRACEPKT0)_16") (pintype "bidirectional"))
    )
    (net (code "64") (name "unconnected-(U401-P1.17(TRACEPKT1)-Pad12)") (class "Default")
      (node (ref "U401") (pin "12") (pinfunction "P1.17(TRACEPKT1)_12") (pintype "bidirectional"))
    )
    (net (code "65") (name "unconnected-(U401-P1.18(TRACEPKT2)-Pad8)") (class "Default")
      (node (ref "U401") (pin "8") (pinfunction "P1.18(TRACEPKT2)_8") (pintype "bidirectional"))
    )
    (net (code "66") (name "unconnected-(U401-P1.19(TRACEPKT3)-Pad4)") (class "Default")
      (node (ref "U401") (pin "4") (pinfunction "P1.19(TRACEPKT3)_4") (pintype "bidirectional"))
    )
    (net (code "67") (name "unconnected-(U401-P1.20(TRACESYNC)-Pad48)") (class "Default")
      (node (ref "U401") (pin "48") (pinfunction "P1.20(TRACESYNC)_48") (pintype "bidirectional"))
    )
    (net (code "68") (name "unconnected-(U401-P1.21(PIPESTAT0)-Pad44)") (class "Default")
      (node (ref "U401") (pin "44") (pinfunction "P1.21(PIPESTAT0)_44") (pintype "bidirectional"))
    )
    (net (code "69") (name "unconnected-(U401-P1.22(PIPESTAT1)-Pad40)") (class "Default")
      (node (ref "U401") (pin "40") (pinfunction "P1.22(PIPESTAT1)_40") (pintype "bidirectional"))
    )
    (net (code "70") (name "unconnected-(U401-P1.23(PIPESTAT2)-Pad36)") (class "Default")
      (node (ref "U401") (pin "36") (pinfunction "P1.23(PIPESTAT2)_36") (pintype "bidirectional"))
    )
    (net (code "71") (name "unconnected-(U401-P1.24(TRACECLK)-Pad32)") (class "Default")
      (node (ref "U401") (pin "32") (pinfunction "P1.24(TRACECLK)_32") (pintype "bidirectional"))
    )
    (net (code "72") (name "unconnected-(U401-P1.25(EXTIN0)-Pad28)") (class "Default")
      (node (ref "U401") (pin "28") (pinfunction "P1.25(EXTIN0)_28") (pintype "bidirectional"))
    )
    (net (code "73") (name "unconnected-(U401-P1.26(RTCK)-Pad24)") (class "Default")
      (node (ref "U401") (pin "24") (pinfunction "P1.26(RTCK)_24") (pintype "bidirectional"))
    )
    (net (code "74") (name "unconnected-(U401-P1.27(TDO)-Pad64)") (class "Default")
      (node (ref "U401") (pin "64") (pinfunction "P1.27(TDO)_64") (pintype "bidirectional"))
    )
    (net (code "75") (name "unconnected-(U401-P1.28(TDI)-Pad60)") (class "Default")
      (node (ref "U401") (pin "60") (pinfunction "P1.28(TDI)_60") (pintype "bidirectional"))
    )
    (net (code "76") (name "unconnected-(U401-P1.29(TCK)-Pad56)") (class "Default")
      (node (ref "U401") (pin "56") (pinfunction "P1.29(TCK)_56") (pintype "bidirectional"))
    )
    (net (code "77") (name "unconnected-(U401-P1.30(TMS)-Pad52)") (class "Default")
      (node (ref "U401") (pin "52") (pinfunction "P1.30(TMS)_52") (pintype "bidirectional"))
    )
    (net (code "78") (name "unconnected-(U401-P1.31({slash}TRST)-Pad20)") (class "Default")
      (node (ref "U401") (pin "20") (pinfunction "P1.31(/TRST)_20") (pintype "bidirectional"))
    )
    (net (code "79") (name "unconnected-(U401-RTXC2-Pad5)") (class "Default")
      (node (ref "U401") (pin "5") (pinfunction "RTXC2_5") (pintype "output"))
    )
    (net (code "80") (name "unconnected-(U501-INT1-Pad7)") (class "Default")
      (node (ref "U501") (pin "7") (pinfunction "INT1_7") (pintype "bidirectional"))
    )
    (net (code "81") (name "unconnected-(U601-INT2-Pad9)") (class "Default")
      (node (ref "U601") (pin "9") (pinfunction "INT2_9") (pintype "bidirectional"))
    )
    (net (code "82") (name "unconnected-(U601-NC-Pad3)") (class "Default")
      (node (ref "U601") (pin "3") (pinfunction "NC_3") (pintype "bidirectional"))
    )
    (net (code "83") (name "unconnected-(U601-NC-Pad10)") (class "Default")
      (node (ref "U601") (pin "10") (pinfunction "NC_10") (pintype "bidirectional"))
    )
    (net (code "84") (name "unconnected-(U601-NC-Pad11)") (class "Default")
      (node (ref "U601") (pin "11") (pinfunction "NC_11") (pintype "bidirectional"))
    )
    (net (code "85") (name "unconnected-(U801-NC-Pad3)") (class "Default")
      (node (ref "U801") (pin "3") (pinfunction "NC_3") (pintype "bidirectional"))
    )
    (net (code "86") (name "unconnected-(U801-NC-Pad5)") (class "Default")
      (node (ref "U801") (pin "5") (pinfunction "NC_5") (pintype "bidirectional"))
    )
    (net (code "87") (name "unconnected-(U801-NC-Pad6)") (class "Default")
      (node (ref "U801") (pin "6") (pinfunction "NC_6") (pintype "bidirectional"))
    )
    (net (code "88") (name "unconnected-(U801-NC-Pad7)") (class "Default")
      (node (ref "U801") (pin "7") (pinfunction "NC_7") (pintype "bidirectional"))
    )
    (net (code "89") (name "unconnected-(U801-NC-Pad14)") (class "Default")
      (node (ref "U801") (pin "14") (pinfunction "NC_14") (pintype "bidirectional"))
    )
  )
)
